# PWR_PROT_AND_VI_SENSE.net
KiCad netlist of a schematic drawn in Altium Designer
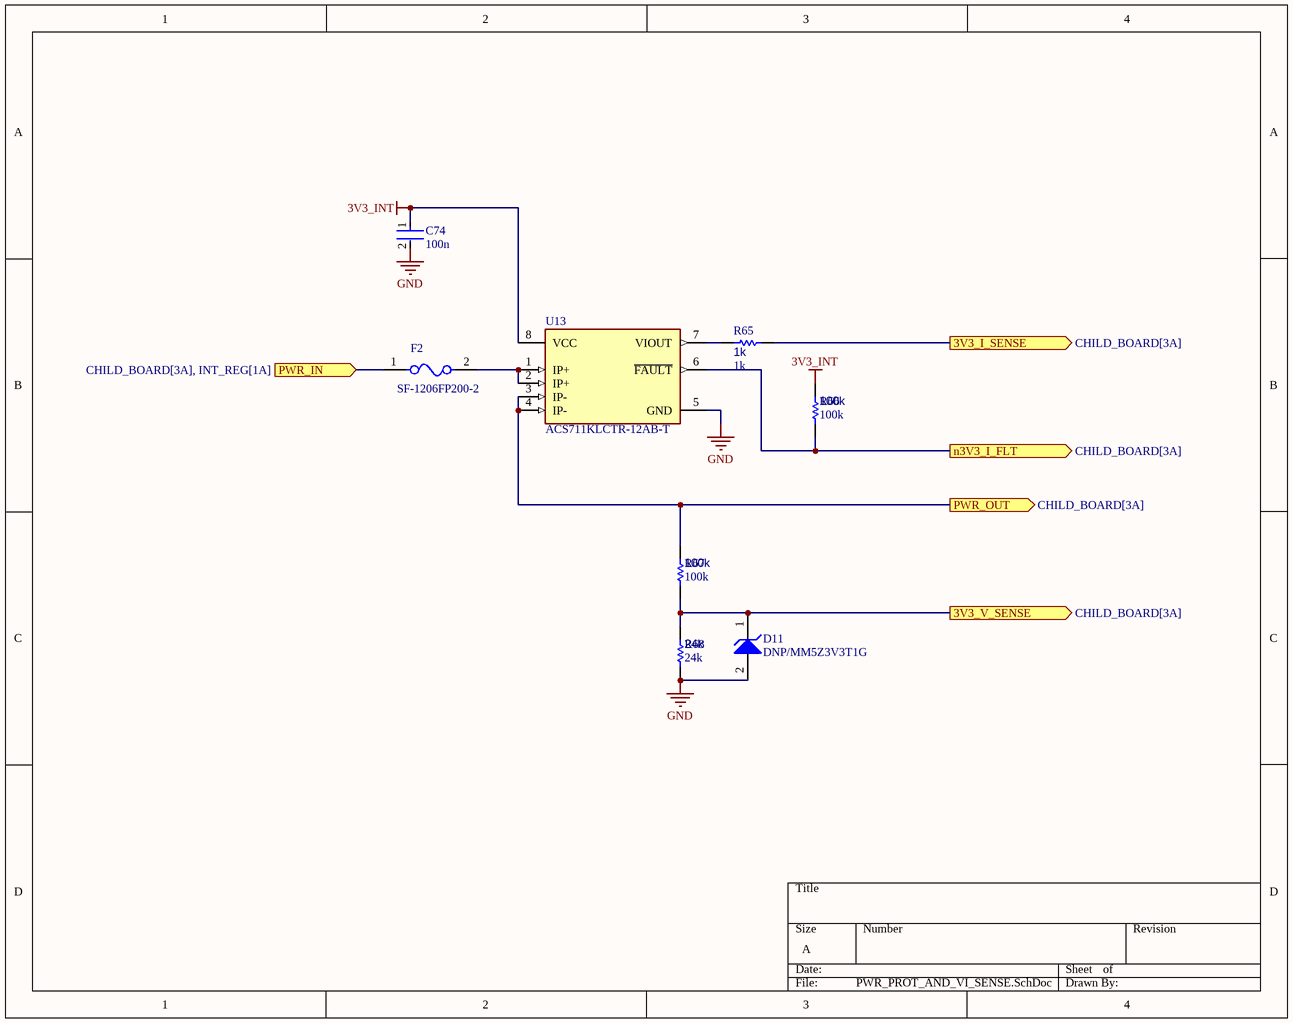
[diagram p0: PWR_PROT_AND_VI_SENSE.SchDoc]

(export (version "E")
  (design (tool "Eeschema 10.0.6"))
  (components
    (comp (ref "C74")
      (value "100n")
      (footprint "FP-0402-L_1_0_0_05-W_0_5-IPC_A")
      (description "LARGE PADS, 0402 CAP, CHANGE COMMENT TO MATCH REAL P/N")
      (libsource (lib "Space Concordia") (part "b4654b650e69147ec39a6b967a45e02"))
    )
    (comp (ref "D11")
      (value "DNP/MM5Z3V3T1G")
      (footprint "ONSC-SOD-523-2-502-01_V")
      (description "Zener Voltage Regulator, 500 mW, 2-Pin SOD-523, Pb-Free, Tape and Reel")
      (fields (field (name "MANUFACTURER") "On Semiconductor") (field (name "PARTNUMBER") "MM5Z3V3T1G"))
      (libsource (lib "Altium Content Vault") (part "ONSC-K1A2-2"))
    )
    (comp (ref "F2")
      (value "SF-1206FP200-2")
      (footprint "FP-SF-1206FP-MFG")
      (description "FUSE BOARD MOUNT 2A 63VDC 1206")
      (libsource (lib "Altium Content Vault") (part "5bcf9b9f640e542cf0359d10258e979"))
    )
    (comp (ref "R65")
      (value "1k")
      (footprint "R0603B")
      (description "Resistor")
      (fields (field (name "ALTIUM_VALUE") "1k"))
      (libsource (lib "Space Concordia") (part "Resistor"))
    )
    (comp (ref "R66")
      (value "100k")
      (footprint "R0603B")
      (description "Resistor")
      (fields (field (name "ALTIUM_VALUE") "100k"))
      (libsource (lib "Space Concordia") (part "Resistor"))
    )
    (comp (ref "R67")
      (value "100k")
      (footprint "R0603B")
      (description "Resistor")
      (fields (field (name "ALTIUM_VALUE") "100k"))
      (libsource (lib "Space Concordia") (part "Resistor"))
    )
    (comp (ref "R68")
      (value "24k")
      (footprint "R0603B")
      (description "Resistor")
      (fields (field (name "ALTIUM_VALUE") "24k"))
      (libsource (lib "Space Concordia") (part "Resistor"))
    )
    (comp (ref "U13")
      (value "ACS711KLCTR-12AB-T")
      (footprint "FP-LC-8-IPC_C")
      (description "SENSOR CURRENT HALL 12.5A AC/DC")
      (libsource (lib "Altium Content Vault") (part "b5e82308d4912bad35d89a98a7a92f9"))
    )
  )
  (nets
    (net (code "1") (name "/3V3_I_SENSE") (class "Default")
      (node (ref "R65") (pin "2") (pinfunction "2_2") (pintype "passive"))
    )
    (net (code "2") (name "/3V3_V_SENSE") (class "Default")
      (node (ref "D11") (pin "1") (pinfunction "K_1") (pintype "passive"))
      (node (ref "R67") (pin "1") (pinfunction "1_1") (pintype "passive"))
      (node (ref "R68") (pin "2") (pinfunction "2_2") (pintype "passive"))
    )
    (net (code "3") (name "/PWR_IN") (class "Default")
      (node (ref "F2") (pin "1") (pinfunction "1_1") (pintype "passive"))
    )
    (net (code "4") (name "/PWR_OUT") (class "Default")
      (node (ref "R67") (pin "2") (pinfunction "2_2") (pintype "passive"))
      (node (ref "U13") (pin "3") (pinfunction "IP-_3") (pintype "input"))
      (node (ref "U13") (pin "4") (pinfunction "IP-_4") (pintype "input"))
    )
    (net (code "5") (name "/n3V3_I_FLT") (class "Default")
      (node (ref "R66") (pin "1") (pinfunction "1_1") (pintype "passive"))
      (node (ref "U13") (pin "6") (pinfunction "~{FAULT}_6") (pintype "output"))
    )
    (net (code "6") (name "3V3_INT") (class "Default")
      (node (ref "C74") (pin "1") (pinfunction "1_1") (pintype "passive"))
      (node (ref "R66") (pin "2") (pinfunction "2_2") (pintype "passive"))
      (node (ref "U13") (pin "8") (pinfunction "VCC_8") (pintype "power_in"))
    )
    (net (code "7") (name "GND") (class "Default")
      (node (ref "C74") (pin "2") (pinfunction "2_2") (pintype "passive"))
      (node (ref "D11") (pin "2") (pinfunction "A_2") (pintype "passive"))
      (node (ref "R68") (pin "1") (pinfunction "1_1") (pintype "passive"))
      (node (ref "U13") (pin "5") (pinfunction "GND_5") (pintype "power_in"))
    )
    (net (code "8") (name "Net-(F2-Pad2)") (class "Default")
      (node (ref "F2") (pin "2") (pinfunction "2_2") (pintype "passive"))
      (node (ref "U13") (pin "1") (pinfunction "IP+_1") (pintype "input"))
      (node (ref "U13") (pin "2") (pinfunction "IP+_2") (pintype "input"))
    )
    (net (code "9") (name "Net-(U13-VIOUT)") (class "Default")
      (node (ref "R65") (pin "1") (pinfunction "1_1") (pintype "passive"))
      (node (ref "U13") (pin "7") (pinfunction "VIOUT_7") (pintype "output"))
    )
  )
)
